# voeding.net
KiCad netlist of a schematic drawn in Altium Designer
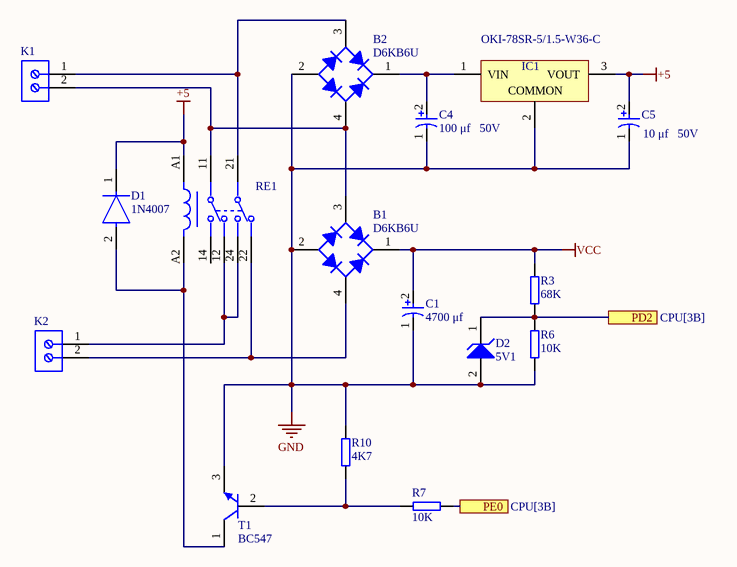
[diagram p0: voeding.SchDoc]

(export (version "E")
  (design (tool "Eeschema 10.0.6"))
  (components
    (comp (ref "B1")
      (value "D6KB6U")
      (footprint "ttf")
      (fields (field (name "MANUFACTURER") "Diodes Inc"))
      (libsource (lib "Soldeerstation_Final") (part "Bridge_Rectifier"))
    )
    (comp (ref "B2")
      (value "D6KB6U")
      (footprint "ttf")
      (fields (field (name "MANUFACTURER") "Diodes Inc"))
      (libsource (lib "Soldeerstation_Final") (part "Bridge_Rectifier"))
    )
    (comp (ref "C1")
      (value "4700 μf")
      (footprint "CE_D8_L10")
      (fields (field (name "MANUFACTURER") "Panasonic"))
      (libsource (lib "Soldeerstation_Final") (part "Capacitor_Electrolytic"))
    )
    (comp (ref "C4")
      (value "100 μf   50V")
      (footprint "CE_D8_L10")
      (fields (field (name "MANUFACTURER") "Panasonic"))
      (libsource (lib "Soldeerstation_Final") (part "Capacitor_Electrolytic"))
    )
    (comp (ref "C5")
      (value "10 μf   50V")
      (footprint "CE_D8_L10")
      (fields (field (name "MANUFACTURER") "Panasonic"))
      (libsource (lib "Soldeerstation_Final") (part "Capacitor_Electrolytic"))
    )
    (comp (ref "D1")
      (value "1N4007")
      (footprint "SOD-123FL")
      (fields
        (field (name "MANUFACTURER") "Diotec")
        (field (name "OCTOPART") "https://octopart.com/1n4007-diotec-4040411")
      )
      (libsource (lib "Soldeerstation_Final") (part "Diode"))
    )
    (comp (ref "D2")
      (value "5V1")
      (footprint "SOD-123FL")
      (fields (field (name "MANUFACTURER") "On Semiconductor") (field (name "PARTNUMBER") "1SMB5920BT3G"))
      (libsource (lib "Soldeerstation_Final") (part "Zener_Diode"))
    )
    (comp (ref "IC1")
      (value "OKI-78SR-5/1.5-W36-C")
      (footprint "OKI78SR515W36C")
      (fields (field (name "MANUFACTURER") "Murata"))
      (libsource (lib "Soldeerstation_Final") (part "DC/DC Converter"))
    )
    (comp (ref "K1")
      (value "~")
      (footprint "TECO-282836-2_V")
      (description "Female Header, Pitch 5 mm, 1 x 2 Position, Height 10 mm, Tail Length 3.5 mm, Rohs, Bulk")
      (fields (field (name "VOLTAGE") "300V") (field (name "MANUFACTURER") "TE Connectivity"))
      (libsource (lib "Soldeerstation_Final") (part "CMP-1684-00017-1"))
    )
    (comp (ref "K2")
      (value "~")
      (footprint "TECO-282836-2_V")
      (description "Female Header, Pitch 5 mm, 1 x 2 Position, Height 10 mm, Tail Length 3.5 mm, Rohs, Bulk")
      (fields (field (name "VOLTAGE") "300V") (field (name "MANUFACTURER") "TE Connectivity"))
      (libsource (lib "Soldeerstation_Final") (part "CMP-1684-00017-1"))
    )
    (comp (ref "R3")
      (value "68K")
      (footprint "0805_M")
      (fields (field (name "MANUFACTURER") "Vishay Dale") (field (name "PART NUMBER") "CRCW08050000Z0EA"))
      (libsource (lib "Soldeerstation_Final") (part "Resistor"))
    )
    (comp (ref "R6")
      (value "10K")
      (footprint "0805_M")
      (fields (field (name "MANUFACTURER") "Vishay Dale") (field (name "PART NUMBER") "CRCW08050000Z0EA"))
      (libsource (lib "Soldeerstation_Final") (part "Resistor"))
    )
    (comp (ref "R7")
      (value "10K")
      (footprint "0805_M")
      (fields (field (name "MANUFACTURER") "Vishay Dale") (field (name "PART NUMBER") "CRCW08050000Z0EA"))
      (libsource (lib "Soldeerstation_Final") (part "Resistor"))
    )
    (comp (ref "R10")
      (value "4K7")
      (footprint "0805_M")
      (fields (field (name "MANUFACTURER") "Vishay Dale") (field (name "PART NUMBER") "CRCW08050000Z0EA"))
      (libsource (lib "Soldeerstation_Final") (part "Resistor"))
    )
    (comp (ref "RE1")
      (value "~")
      (footprint "RT42")
      (fields
        (field (name "MANUFACTURER PART NUMBER") "RT424005")
        (field (name "OCTOPART") "https://octopart.com/5-1393243-9-te+connectivity-41835766")
        (field (name "MANUFACTURER") "TE Connectivity")
      )
      (libsource (lib "Soldeerstation_Final") (part "RELAY_GENERAL_PURPOSE"))
    )
    (comp (ref "T1")
      (value "BC547")
      (footprint "SOT_23")
      (fields (field (name "MANUFACTURER") "On Semiconductor") (field (name "PARTNUMBER") "BC547C"))
      (libsource (lib "Soldeerstation_Final") (part "Transistor_NPN"))
    )
  )
  (nets
    (net (code "1") (name "+5") (class "Default")
      (node (ref "C5") (pin "2") (pinfunction "2_2") (pintype "passive"))
      (node (ref "D1") (pin "1") (pinfunction "C_1") (pintype "passive"))
      (node (ref "IC1") (pin "3") (pinfunction "VOUT_3") (pintype "power_in"))
      (node (ref "RE1") (pin "A1") (pinfunction "A1_A1") (pintype "passive"))
    )
    (net (code "2") (name "/PD2") (class "Default")
      (node (ref "D2") (pin "1") (pinfunction "K_1") (pintype "passive"))
      (node (ref "R3") (pin "1") (pinfunction "1_1") (pintype "passive"))
      (node (ref "R6") (pin "2") (pinfunction "2_2") (pintype "passive"))
    )
    (net (code "3") (name "/PE0") (class "Default")
      (node (ref "R7") (pin "1") (pinfunction "1_1") (pintype "passive"))
    )
    (net (code "4") (name "GND") (class "Default")
      (node (ref "B1") (pin "2") (pinfunction "A_2") (pintype "passive"))
      (node (ref "B2") (pin "2") (pinfunction "A_2") (pintype "passive"))
      (node (ref "C1") (pin "1") (pinfunction "1_1") (pintype "passive"))
      (node (ref "C4") (pin "1") (pinfunction "1_1") (pintype "passive"))
      (node (ref "C5") (pin "1") (pinfunction "1_1") (pintype "passive"))
      (node (ref "D2") (pin "2") (pinfunction "A_2") (pintype "passive"))
      (node (ref "IC1") (pin "2") (pinfunction "COMMON_2") (pintype "power_in"))
      (node (ref "R10") (pin "2") (pinfunction "2_2") (pintype "passive"))
      (node (ref "R6") (pin "1") (pinfunction "1_1") (pintype "passive"))
      (node (ref "T1") (pin "3") (pinfunction "E_3") (pintype "passive"))
    )
    (net (code "5") (name "Net-(B1-C-Pad3)") (class "Default")
      (node (ref "B1") (pin "3") (pinfunction "C_3") (pintype "passive"))
      (node (ref "B2") (pin "4") (pinfunction "C_4") (pintype "passive"))
      (node (ref "K1") (pin "2") (pinfunction "2_2") (pintype "passive"))
      (node (ref "RE1") (pin "11") (pinfunction "11_11") (pintype "passive"))
    )
    (net (code "6") (name "Net-(B1-C-Pad4)") (class "Default")
      (node (ref "B1") (pin "4") (pinfunction "C_4") (pintype "passive"))
      (node (ref "K2") (pin "2") (pinfunction "2_2") (pintype "passive"))
      (node (ref "RE1") (pin "22") (pinfunction "22_22") (pintype "passive"))
    )
    (net (code "7") (name "Net-(B2-C-Pad3)") (class "Default")
      (node (ref "B2") (pin "3") (pinfunction "C_3") (pintype "passive"))
      (node (ref "K1") (pin "1") (pinfunction "1_1") (pintype "passive"))
      (node (ref "RE1") (pin "21") (pinfunction "21_21") (pintype "passive"))
    )
    (net (code "8") (name "Net-(B2-K)") (class "Default")
      (node (ref "B2") (pin "1") (pinfunction "K_1") (pintype "passive"))
      (node (ref "C4") (pin "2") (pinfunction "2_2") (pintype "passive"))
      (node (ref "IC1") (pin "1") (pinfunction "VIN_1") (pintype "power_in"))
    )
    (net (code "9") (name "Net-(D1-A)") (class "Default")
      (node (ref "D1") (pin "2") (pinfunction "A_2") (pintype "passive"))
      (node (ref "RE1") (pin "A2") (pinfunction "A2_A2") (pintype "passive"))
      (node (ref "T1") (pin "1") (pinfunction "C_1") (pintype "passive"))
    )
    (net (code "10") (name "Net-(K2-Pad1)") (class "Default")
      (node (ref "K2") (pin "1") (pinfunction "1_1") (pintype "passive"))
      (node (ref "RE1") (pin "12") (pinfunction "12_12") (pintype "passive"))
      (node (ref "RE1") (pin "24") (pinfunction "24_24") (pintype "passive"))
    )
    (net (code "11") (name "Net-(T1-B)") (class "Default")
      (node (ref "R10") (pin "1") (pinfunction "1_1") (pintype "passive"))
      (node (ref "R7") (pin "2") (pinfunction "2_2") (pintype "passive"))
      (node (ref "T1") (pin "2") (pinfunction "B_2") (pintype "passive"))
    )
    (net (code "12") (name "VCC") (class "Default")
      (node (ref "B1") (pin "1") (pinfunction "K_1") (pintype "passive"))
      (node (ref "C1") (pin "2") (pinfunction "2_2") (pintype "passive"))
      (node (ref "R3") (pin "2") (pinfunction "2_2") (pintype "passive"))
    )
    (net (code "13") (name "unconnected-(RE1-Pad14)") (class "Default")
      (node (ref "RE1") (pin "14") (pinfunction "14_14") (pintype "passive"))
    )
  )
)
